# MCU089A_XDS110_USB_Power.net
KiCad netlist of a schematic drawn in Altium Designer
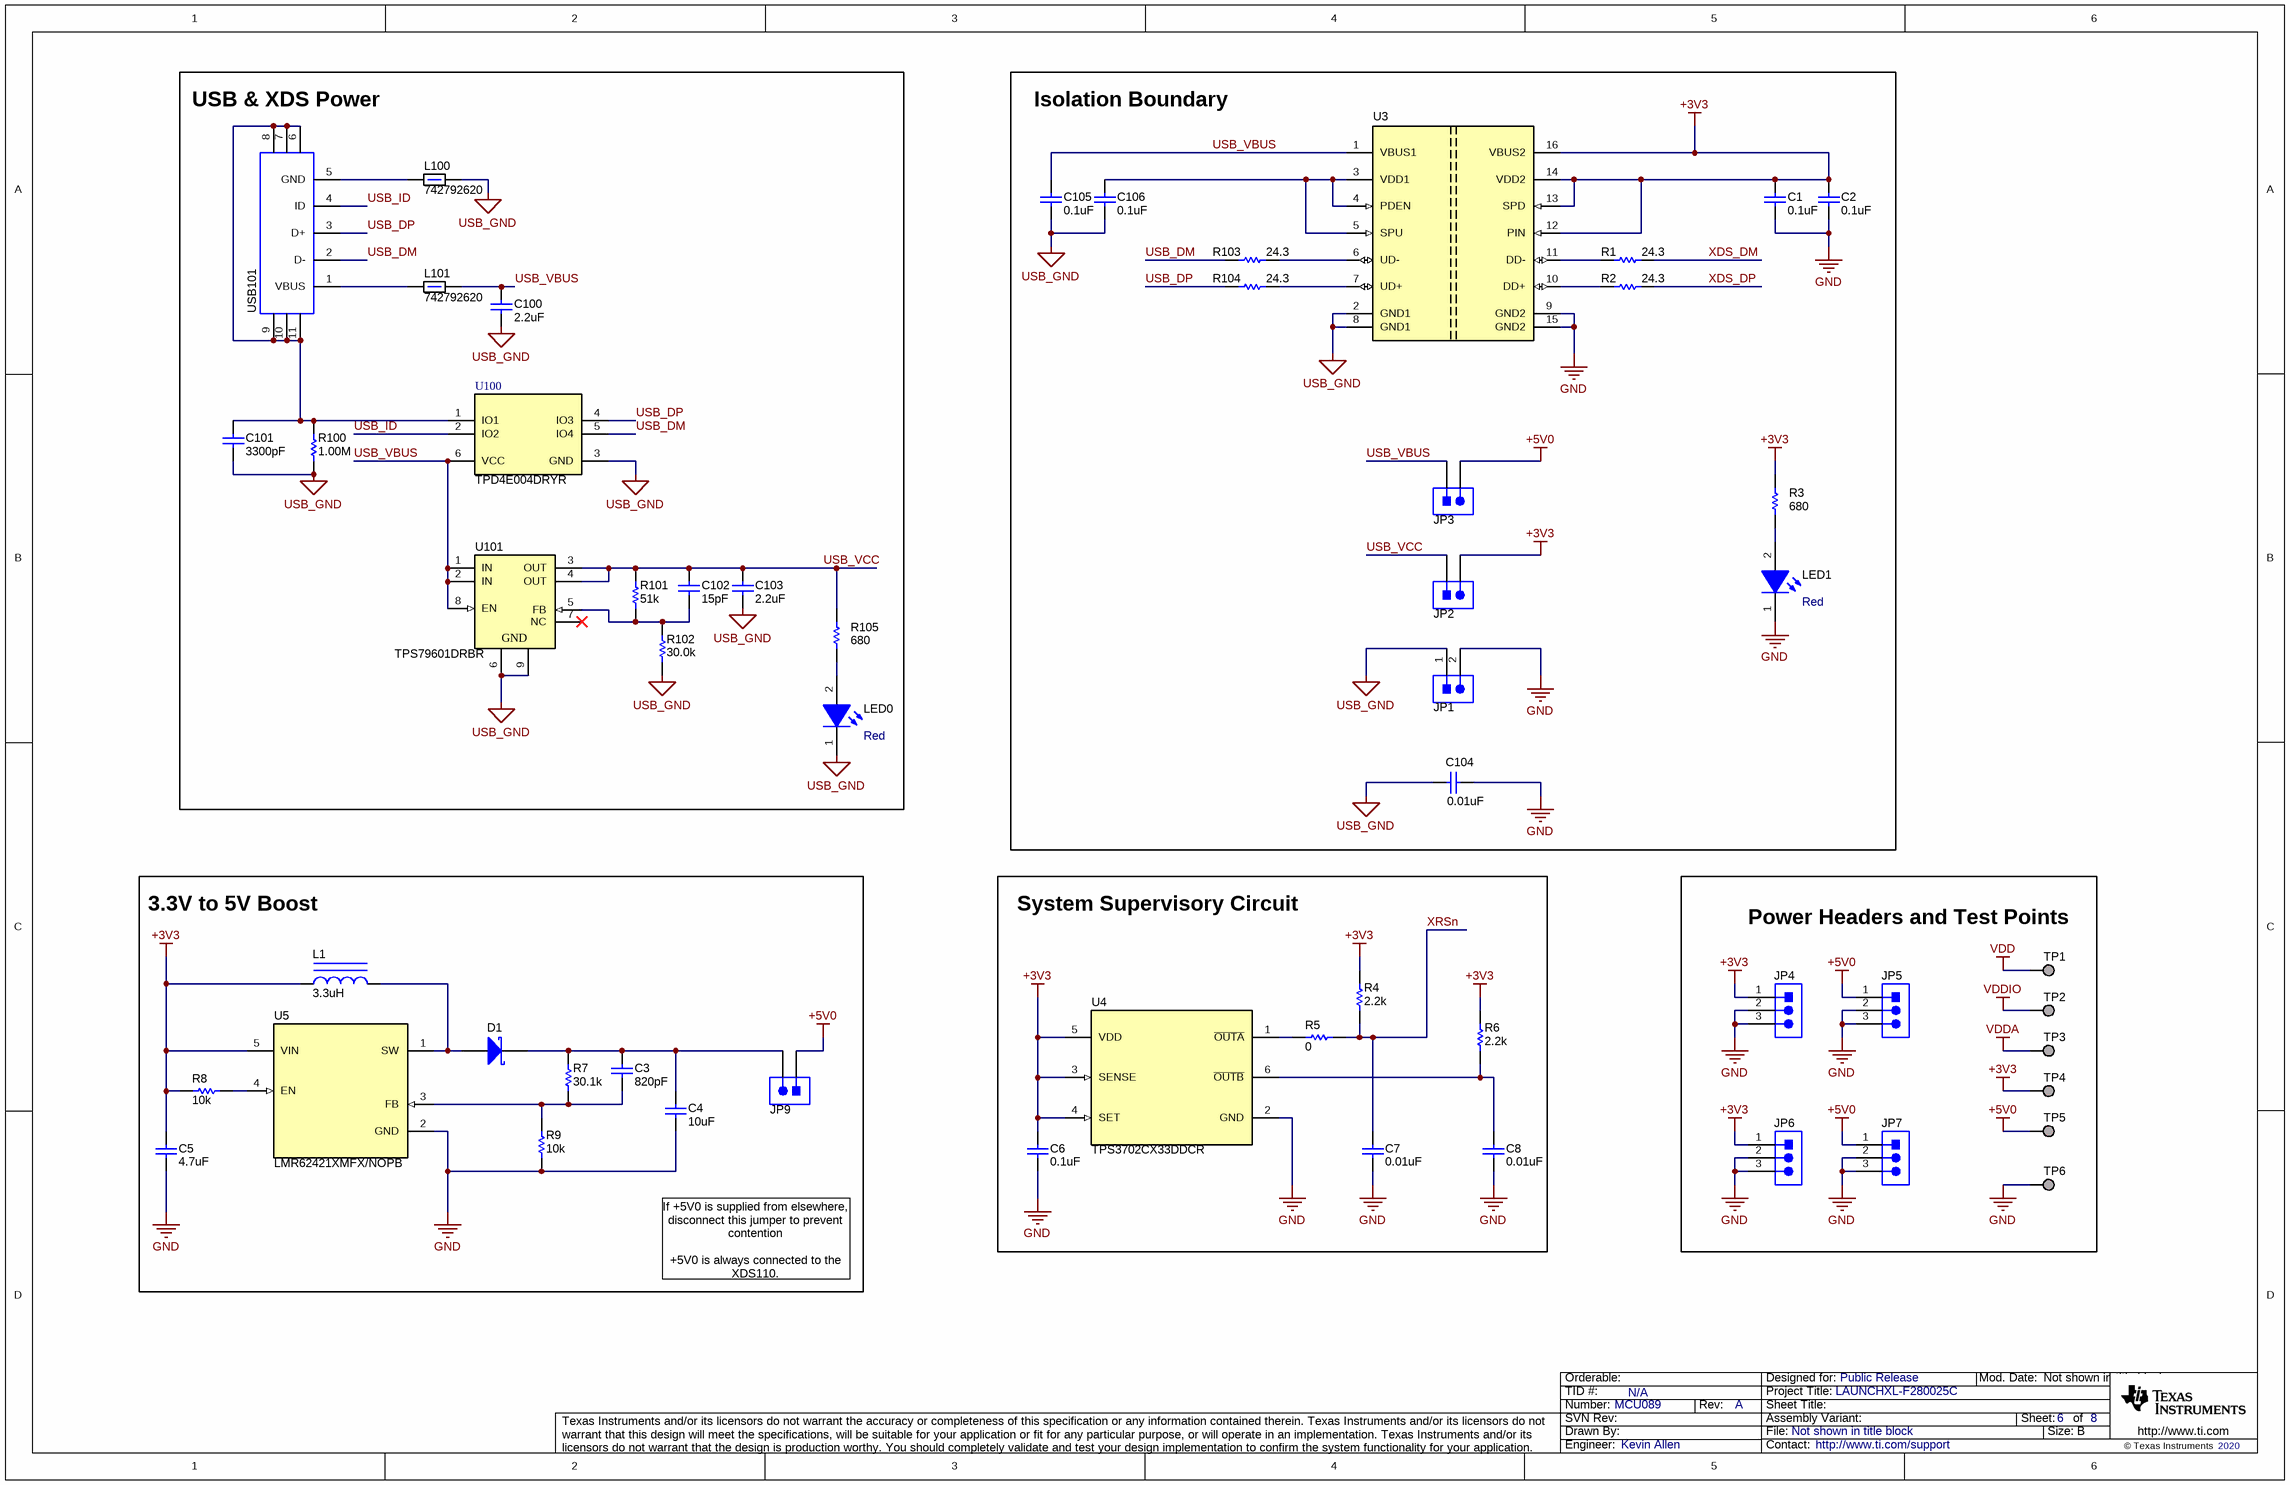
[diagram p0: MCU089A_XDS110_USB_Power.SchDoc]

(export (version "E")
  (design (tool "Eeschema 10.0.6"))
  (components
    (comp (ref "C1")
      (value "GRM155R71A104KA01D")
      (footprint "0402")
      (description "CAP, CERM, 0.1 uF, 10 V, +/- 10%, X7R, 0402")
      (fields
        (field (name "VALUEDISPLAYED") "0.1uF")
        (field (name "MANUFACTURER") "MuRata")
        (field (name "PUBLISHER") "Texas Instruments")
      )
      (libsource (lib "Altium Vault - TI") (part "Capacitor"))
    )
    (comp (ref "C2")
      (value "GRM155R71A104KA01D")
      (footprint "0402")
      (description "CAP, CERM, 0.1 uF, 10 V, +/- 10%, X7R, 0402")
      (fields
        (field (name "VALUEDISPLAYED") "0.1uF")
        (field (name "MANUFACTURER") "MuRata")
        (field (name "PUBLISHER") "Texas Instruments")
      )
      (libsource (lib "Altium Vault - TI") (part "Capacitor"))
    )
    (comp (ref "C3")
      (value "GRM1555C1E821JA01D")
      (footprint "0402")
      (description "CAP, CERM, 820 pF, 25 V, +/- 5%, C0G/NP0, 0402")
      (fields
        (field (name "MANUFACTURER") "MuRata")
        (field (name "VALUEDISPLAYED") "820pF")
        (field (name "PUBLISHER") "Texas Instruments")
      )
      (libsource (lib "Altium Vault - TI") (part "Capacitor"))
    )
    (comp (ref "C4")
      (value "885012209028")
      (footprint "1210_220")
      (description "CAP, CERM, 10 uF, 25 V,+/- 10%, X7R, 1210")
      (fields
        (field (name "VALUEDISPLAYED") "10uF")
        (field (name "MANUFACTURER") "Wurth Elektronik")
        (field (name "PUBLISHER") "Texas Instruments")
      )
      (libsource (lib "Altium Vault - TI") (part "Capacitor"))
    )
    (comp (ref "C5")
      (value "885012105008")
      (footprint "0402")
      (description "CAP, CERM, 4.7 uF, 6.3 V, +/- 20%, X5R, 0402")
      (fields
        (field (name "VALUEDISPLAYED") "4.7uF")
        (field (name "MANUFACTURER") "Wurth Elektronik")
        (field (name "PUBLISHER") "Texas Instruments")
      )
      (libsource (lib "Altium Vault - TI") (part "Capacitor"))
    )
    (comp (ref "C6")
      (value "GRM155R71A104KA01D")
      (footprint "0402")
      (description "CAP, CERM, 0.1 uF, 10 V, +/- 10%, X7R, 0402")
      (fields
        (field (name "VALUEDISPLAYED") "0.1uF")
        (field (name "MANUFACTURER") "MuRata")
        (field (name "PUBLISHER") "Texas Instruments")
      )
      (libsource (lib "Altium Vault - TI") (part "Capacitor"))
    )
    (comp (ref "C7")
      (value "GRM155R71E103KA01D")
      (footprint "0402")
      (description "CAP, CERM, 0.01 uF, 25 V, +/- 10%, X7R, 0402")
      (fields
        (field (name "VALUEDISPLAYED") "0.01uF")
        (field (name "MANUFACTURER") "MuRata")
        (field (name "PUBLISHER") "Texas Instruments")
      )
      (libsource (lib "Altium Vault - TI") (part "Capacitor"))
    )
    (comp (ref "C8")
      (value "GRM155R71E103KA01D")
      (footprint "0402")
      (description "CAP, CERM, 0.01 uF, 25 V, +/- 10%, X7R, 0402")
      (fields
        (field (name "VALUEDISPLAYED") "0.01uF")
        (field (name "MANUFACTURER") "MuRata")
        (field (name "PUBLISHER") "Texas Instruments")
      )
      (libsource (lib "Altium Vault - TI") (part "Capacitor"))
    )
    (comp (ref "C100")
      (value "GRM155R60J225KE95D")
      (footprint "0402")
      (description "CAP, CERM, 2.2 uF, 6.3 V, +/- 10%, X5R, 0402")
      (fields
        (field (name "VALUEDISPLAYED") "2.2uF")
        (field (name "MANUFACTURER") "MuRata")
        (field (name "PUBLISHER") "Texas Instruments")
      )
      (libsource (lib "Altium Vault - TI") (part "Capacitor"))
    )
    (comp (ref "C101")
      (value "GRM155R71H332KA01D")
      (footprint "0402")
      (description "CAP, CERM, 3300 pF, 50 V, +/- 10%, X7R, 0402")
      (fields
        (field (name "VALUEDISPLAYED") "3300pF")
        (field (name "MANUFACTURER") "MuRata")
        (field (name "PUBLISHER") "Texas Instruments")
      )
      (libsource (lib "Altium Vault - TI") (part "Capacitor"))
    )
    (comp (ref "C102")
      (value "885012005056")
      (footprint "0402")
      (description "CAP, CERM, 15 pF, 50 V, +/- 5%, C0G/NP0, 0402")
      (fields
        (field (name "VALUEDISPLAYED") "15pF")
        (field (name "MANUFACTURER") "Wurth Elektronik")
        (field (name "PUBLISHER") "Texas Instruments")
      )
      (libsource (lib "Altium Vault - TI") (part "Capacitor"))
    )
    (comp (ref "C103")
      (value "GRM155R60J225KE95D")
      (footprint "0402")
      (description "CAP, CERM, 2.2 uF, 6.3 V, +/- 10%, X5R, 0402")
      (fields
        (field (name "VALUEDISPLAYED") "2.2uF")
        (field (name "MANUFACTURER") "MuRata")
        (field (name "PUBLISHER") "Texas Instruments")
      )
      (libsource (lib "Altium Vault - TI") (part "Capacitor"))
    )
    (comp (ref "C104")
      (value "1812SC103KAT1A")
      (footprint "1812")
      (description "CAP, CERM, 0.01 uF, 1500 V, +/- 10%, X7R, 1812")
      (fields
        (field (name "MANUFACTURER") "AVX")
        (field (name "VALUEDISPLAYED") "0.01uF")
        (field (name "PUBLISHER") "Texas Instruments")
      )
      (libsource (lib "Altium Vault - TI") (part "Capacitor"))
    )
    (comp (ref "C105")
      (value "GRM155R71A104KA01D")
      (footprint "0402")
      (description "CAP, CERM, 0.1 uF, 10 V, +/- 10%, X7R, 0402")
      (fields
        (field (name "VALUEDISPLAYED") "0.1uF")
        (field (name "MANUFACTURER") "MuRata")
        (field (name "PUBLISHER") "Texas Instruments")
      )
      (libsource (lib "Altium Vault - TI") (part "Capacitor"))
    )
    (comp (ref "C106")
      (value "GRM155R71A104KA01D")
      (footprint "0402")
      (description "CAP, CERM, 0.1 uF, 10 V, +/- 10%, X7R, 0402")
      (fields
        (field (name "VALUEDISPLAYED") "0.1uF")
        (field (name "MANUFACTURER") "MuRata")
        (field (name "PUBLISHER") "Texas Instruments")
      )
      (libsource (lib "Altium Vault - TI") (part "Capacitor"))
    )
    (comp (ref "D1")
      (value "1N5819HW-7-F")
      (footprint "SOD-123")
      (description "Diode, Schottky, 40 V, 1 A, SOD-123")
      (fields (field (name "MANUFACTURER") "Diodes Inc."))
      (libsource (lib "Altium Vault - TI") (part "DIODE_SCHOTTKY"))
    )
    (comp (ref "JP1")
      (value "61300211121")
      (footprint "WURTH_61300211121")
      (description "Header, 2.54 mm, 2x1, Gold, TH")
      (fields (field (name "MANUFACTURER") "Wurth Elektronik") (field (name "PUBLISHER") "Texas Instruments"))
      (libsource (lib "Altium Vault - TI") (part "Header_2x1"))
    )
    (comp (ref "JP2")
      (value "61300211121")
      (footprint "WURTH_61300211121")
      (description "Header, 2.54 mm, 2x1, Gold, TH")
      (fields (field (name "MANUFACTURER") "Wurth Elektronik") (field (name "PUBLISHER") "Texas Instruments"))
      (libsource (lib "") (part "CMP-0054794-1_1"))
    )
    (comp (ref "JP3")
      (value "61300211121")
      (footprint "WURTH_61300211121")
      (description "Header, 2.54 mm, 2x1, Gold, TH")
      (fields (field (name "MANUFACTURER") "Wurth Elektronik") (field (name "PUBLISHER") "Texas Instruments"))
      (libsource (lib "") (part "CMP-0054794-1_1"))
    )
    (comp (ref "JP4")
      (value "61300311121")
      (footprint "WURTH_61300311121")
      (description "Header, 2.54 mm, 3x1, Gold, TH")
      (fields (field (name "MANUFACTURER") "Wurth Elektronik") (field (name "PUBLISHER") "Texas Instruments"))
      (libsource (lib "Altium Vault - TI") (part "Header_3x1"))
    )
    (comp (ref "JP5")
      (value "61300311121")
      (footprint "WURTH_61300311121")
      (description "Header, 2.54 mm, 3x1, Gold, TH")
      (fields (field (name "MANUFACTURER") "Wurth Elektronik") (field (name "PUBLISHER") "Texas Instruments"))
      (libsource (lib "Altium Vault - TI") (part "Header_3x1"))
    )
    (comp (ref "JP6")
      (value "61300311121")
      (footprint "WURTH_61300311121")
      (description "Header, 2.54 mm, 3x1, Gold, TH")
      (fields (field (name "MANUFACTURER") "Wurth Elektronik") (field (name "PUBLISHER") "Texas Instruments"))
      (libsource (lib "Altium Vault - TI") (part "Header_3x1"))
    )
    (comp (ref "JP7")
      (value "61300311121")
      (footprint "WURTH_61300311121")
      (description "Header, 2.54 mm, 3x1, Gold, TH")
      (fields (field (name "MANUFACTURER") "Wurth Elektronik") (field (name "PUBLISHER") "Texas Instruments"))
      (libsource (lib "Altium Vault - TI") (part "Header_3x1"))
    )
    (comp (ref "JP9")
      (value "61300211121")
      (footprint "WURTH_61300211121")
      (description "Header, 2.54 mm, 2x1, Gold, TH")
      (fields (field (name "MANUFACTURER") "Wurth Elektronik") (field (name "PUBLISHER") "Texas Instruments"))
      (libsource (lib "Altium Vault - TI") (part "CMP-0054794-1"))
    )
    (comp (ref "L1")
      (value "744025003")
      (footprint "WE-TPC_2828")
      (description "Inductor, Shielded Drum Core, Ferrite, 3.3 uH, 1.5 A, 0.085 ohm, SMD")
      (fields
        (field (name "VALUEDISPLAYED") "3.3uH")
        (field (name "MANUFACTURER") "Wurth Elektronik")
        (field (name "PUBLISHER") "Texas Instruments")
      )
      (libsource (lib "Altium Vault - TI") (part "Inductor_Iron"))
    )
    (comp (ref "L100")
      (value "742792620")
      (footprint "0603")
      (description "Ferrite Bead, 100 ohm @ 100 MHz, 0.5 A, 0603")
      (fields (field (name "MANUFACTURER") "Wurth Elektronik") (field (name "PUBLISHER") "Texas Instruments"))
      (libsource (lib "Altium Vault - TI") (part "Ferrite_Bead"))
    )
    (comp (ref "L101")
      (value "742792620")
      (footprint "0603")
      (description "Ferrite Bead, 100 ohm @ 100 MHz, 0.5 A, 0603")
      (fields (field (name "MANUFACTURER") "Wurth Elektronik") (field (name "PUBLISHER") "Texas Instruments"))
      (libsource (lib "Altium Vault - TI") (part "Ferrite_Bead"))
    )
    (comp (ref "LED0")
      (value "Red")
      (footprint "WL-SMCW_RED_0805")
      (description "LED, Red, SMD")
      (fields (field (name "MANUFACTURER") "Wurth Elektronik") (field (name "PARTNUMBER") "150080SS75000"))
      (libsource (lib "Altium Vault - TI") (part "LED_A2_K1"))
    )
    (comp (ref "LED1")
      (value "Red")
      (footprint "WL-SMCW_RED_0805")
      (description "LED, Red, SMD")
      (fields (field (name "MANUFACTURER") "Wurth Elektronik") (field (name "PARTNUMBER") "150080SS75000"))
      (libsource (lib "Altium Vault - TI") (part "LED_A2_K1"))
    )
    (comp (ref "R1")
      (value "CRCW040224R3FKED")
      (footprint "0402")
      (description "RES, 24.3, 1%, 0.063 W, AEC-Q200 Grade 0, 0402")
      (fields (field (name "VALUEDISPLAYED") "24.3") (field (name "MANUFACTURER") "Vishay-Dale"))
      (libsource (lib "Altium Vault - TI") (part "Resistor"))
    )
    (comp (ref "R2")
      (value "CRCW040224R3FKED")
      (footprint "0402")
      (description "RES, 24.3, 1%, 0.063 W, AEC-Q200 Grade 0, 0402")
      (fields (field (name "VALUEDISPLAYED") "24.3") (field (name "MANUFACTURER") "Vishay-Dale"))
      (libsource (lib "Altium Vault - TI") (part "Resistor"))
    )
    (comp (ref "R3")
      (value "CRCW0402680RJNED")
      (footprint "0402")
      (description "RES, 680, 5%, 0.063 W, AEC-Q200 Grade 0, 0402")
      (fields (field (name "MANUFACTURER") "Vishay-Dale") (field (name "VALUEDISPLAYED") "680"))
      (libsource (lib "Altium Vault - TI") (part "CMP-0026962-3"))
    )
    (comp (ref "R4")
      (value "CRCW04022K20JNED")
      (footprint "0402")
      (description "RES, 2.2 k, 5%, 0.063 W, AEC-Q200 Grade 0, 0402")
      (fields (field (name "VALUEDISPLAYED") "2.2k") (field (name "MANUFACTURER") "Vishay-Dale"))
      (libsource (lib "Altium Vault - TI") (part "Resistor"))
    )
    (comp (ref "R5")
      (value "CRCW04020000Z0ED")
      (footprint "0402")
      (description "RES, 0, 5%, 0.063 W, AEC-Q200 Grade 0, 0402")
      (fields (field (name "VALUEDISPLAYED") "0") (field (name "MANUFACTURER") "Vishay-Dale"))
      (libsource (lib "Altium Vault - TI") (part "Resistor"))
    )
    (comp (ref "R6")
      (value "CRCW06032K20JNEA")
      (footprint "0603")
      (description "RES, 2.2 k, 5%, 0.1 W, AEC-Q200 Grade 0, 0603")
      (fields (field (name "VALUEDISPLAYED") "2.2k") (field (name "MANUFACTURER") "Vishay-Dale"))
      (libsource (lib "Altium Vault - TI") (part "Resistor"))
    )
    (comp (ref "R7")
      (value "RC0402FR-0730K1L")
      (footprint "0402")
      (description "RES, 30.1 k, 1%, 0.063 W, 0402")
      (fields
        (field (name "VALUEDISPLAYED") "30.1k")
        (field (name "MANUFACTURER") "Yageo America")
        (field (name "PUBLISHER") "Texas Instruments")
      )
      (libsource (lib "Altium Vault - TI") (part "Resistor"))
    )
    (comp (ref "R8")
      (value "CRCW040210K0JNED")
      (footprint "0402")
      (description "RES, 10 k, 5%, 0.063 W, AEC-Q200 Grade 0, 0402")
      (fields (field (name "VALUEDISPLAYED") "10k") (field (name "MANUFACTURER") "Vishay-Dale"))
      (libsource (lib "Altium Vault - TI") (part "Resistor"))
    )
    (comp (ref "R9")
      (value "CRCW040210K0JNED")
      (footprint "0402")
      (description "RES, 10 k, 5%, 0.063 W, AEC-Q200 Grade 0, 0402")
      (fields (field (name "VALUEDISPLAYED") "10k") (field (name "MANUFACTURER") "Vishay-Dale"))
      (libsource (lib "Altium Vault - TI") (part "Resistor"))
    )
    (comp (ref "R100")
      (value "CRCW04021M00FKED")
      (footprint "0402")
      (description "RES, 1.00 M, 1%, 0.063 W, AEC-Q200 Grade 0, 0402")
      (fields (field (name "VALUEDISPLAYED") "1.00M") (field (name "MANUFACTURER") "Vishay-Dale"))
      (libsource (lib "Altium Vault - TI") (part "Resistor"))
    )
    (comp (ref "R101")
      (value "CRCW040251K0FKED")
      (footprint "0402")
      (description "RES Thick Film SMD 51kΩ 1% 1/16W 0402 100ppm/K")
      (fields (field (name "MANUFACTURER") "Vishay") (field (name "VALUEDISPLAYED") "51k"))
      (libsource (lib "Altium Vault - TI") (part "Resistor"))
    )
    (comp (ref "R102")
      (value "CRCW040230K0FKED")
      (footprint "0402")
      (description "RES, 30.0 k, 1%, 0.063 W, AEC-Q200 Grade 0, 0402")
      (fields (field (name "MANUFACTURER") "Vishay-Dale") (field (name "VALUEDISPLAYED") "30.0k"))
      (libsource (lib "Altium Vault - TI") (part "Resistor"))
    )
    (comp (ref "R103")
      (value "CRCW040224R3FKED")
      (footprint "0402")
      (description "RES, 24.3, 1%, 0.063 W, AEC-Q200 Grade 0, 0402")
      (fields (field (name "VALUEDISPLAYED") "24.3") (field (name "MANUFACTURER") "Vishay-Dale"))
      (libsource (lib "Altium Vault - TI") (part "Resistor"))
    )
    (comp (ref "R104")
      (value "CRCW040224R3FKED")
      (footprint "0402")
      (description "RES, 24.3, 1%, 0.063 W, AEC-Q200 Grade 0, 0402")
      (fields (field (name "VALUEDISPLAYED") "24.3") (field (name "MANUFACTURER") "Vishay-Dale"))
      (libsource (lib "Altium Vault - TI") (part "Resistor"))
    )
    (comp (ref "R105")
      (value "CRCW0402680RJNED")
      (footprint "0402")
      (description "RES, 680, 5%, 0.063 W, AEC-Q200 Grade 0, 0402")
      (fields (field (name "MANUFACTURER") "Vishay-Dale") (field (name "VALUEDISPLAYED") "680"))
      (libsource (lib "Altium Vault - TI") (part "CMP-0026962-3"))
    )
    (comp (ref "TP1")
      (value "TESTPOINT")
      (footprint "TP_50MIL-25MILHOLE")
      (description "TEST POINT.  No entry in BOM.")
      (libsource (lib "Altium Vault - TI") (part "TESTPOINT"))
    )
    (comp (ref "TP2")
      (value "TESTPOINT")
      (footprint "TP_50MIL-25MILHOLE")
      (description "TEST POINT.  No entry in BOM.")
      (libsource (lib "Altium Vault - TI") (part "TESTPOINT"))
    )
    (comp (ref "TP3")
      (value "TESTPOINT")
      (footprint "TP_50MIL-25MILHOLE")
      (description "TEST POINT.  No entry in BOM.")
      (libsource (lib "Altium Vault - TI") (part "TESTPOINT"))
    )
    (comp (ref "TP4")
      (value "TESTPOINT")
      (footprint "TP_50MIL-25MILHOLE")
      (description "TEST POINT.  No entry in BOM.")
      (libsource (lib "Altium Vault - TI") (part "TESTPOINT"))
    )
    (comp (ref "TP5")
      (value "TESTPOINT")
      (footprint "TP_50MIL-25MILHOLE")
      (description "TEST POINT.  No entry in BOM.")
      (libsource (lib "Altium Vault - TI") (part "TESTPOINT"))
    )
    (comp (ref "TP6")
      (value "TESTPOINT")
      (footprint "TP_50MIL-25MILHOLE")
      (description "TEST POINT.  No entry in BOM.")
      (libsource (lib "Altium Vault - TI") (part "TESTPOINT"))
    )
    (comp (ref "U3")
      (value "ADuM3160BRWZ")
      (footprint "SOIC-16")
      (description "Full/Low Speed 2.5 kV USB Digital Isolator, SOIC-16")
      (fields (field (name "MANUFACTURER") "Analog Devices") (field (name "PUBLISHER") "Texas Instruments"))
      (libsource (lib "Altium Vault - TI") (part "ADuM3160"))
    )
    (comp (ref "U4")
      (value "TPS3702CX33DDCR")
      (footprint "DDC0006A_N")
      (description "High-Accuracy, Fixed-Threshold OV/UV Monitor, DDC0006A (SOT-23-T-6)")
      (fields
        (field (name "ALTERNATE PARTNUMBER") "TPS3702CX33DDCT")
        (field (name "MANUFACTURER") "Texas Instruments")
        (field (name "PUBLISHER") "Texas Instruments")
      )
      (libsource (lib "Altium Vault - TI") (part "TPS3702"))
    )
    (comp (ref "U5")
      (value "LMR62421XMFX/NOPB")
      (footprint "DBV0005A_N")
      (description "SIMPLE SWITCHER 2.7V to 5.5V, 2.1A Step-Up Regulator in SOT-23, DBV0005A (SOT-23-5)")
      (fields
        (field (name "ALTERNATE PARTNUMBER") "LMR62421XMFE/NOPB")
        (field (name "MANUFACTURER") "Texas Instruments")
        (field (name "PUBLISHER") "Texas Instruments")
      )
      (libsource (lib "Altium Vault - TI") (part "LMR62421DBV"))
    )
    (comp (ref "U100")
      (value "TPD4E004DRYR")
      (footprint "DRY0006A")
      (description "4-Channel ESD Protection Array for High-Speed Data Interfaces, DRY0006A (USON-6)")
      (fields (field (name "MANUFACTURER") "Texas Instruments") (field (name "PARTNUMBER") "TPD4E004DRYR"))
      (libsource (lib "Altium Vault - TI") (part "TI-TPD4E004-SON_DRY-6"))
    )
    (comp (ref "U101")
      (value "TPS79601DRBR")
      (footprint "DRB0008B")
      (fields (field (name "MANUFACTURER") "Texas Instruments"))
      (libsource (lib "Altium Vault - TI") (part "CMP-0036402-3"))
    )
    (comp (ref "USB101")
      (value "1051640001")
      (footprint "Molex_1051640001")
      (description "Receptacle, USB 2.0, Micro B, 5 Position, R/A, SMT")
      (fields (field (name "MANUFACTURER") "Molex") (field (name "PUBLISHER") "Texas Instruments"))
      (libsource (lib "Altium Vault - TI") (part "CONN_USB_MicroMini_6Shld"))
    )
  )
  (nets
    (net (code "1") (name "+3V3") (class "Default")
      (node (ref "C1") (pin "2") (pinfunction "2_2") (pintype "passive"))
      (node (ref "C2") (pin "2") (pinfunction "2_2") (pintype "passive"))
      (node (ref "C5") (pin "1") (pinfunction "1_1") (pintype "passive"))
      (node (ref "C6") (pin "2") (pinfunction "2_2") (pintype "passive"))
      (node (ref "JP2") (pin "2") (pinfunction "2_2") (pintype "passive"))
      (node (ref "JP4") (pin "1") (pinfunction "1_1") (pintype "passive"))
      (node (ref "JP6") (pin "1") (pinfunction "1_1") (pintype "passive"))
      (node (ref "L1") (pin "1") (pinfunction "1_1") (pintype "passive"))
      (node (ref "R3") (pin "2") (pinfunction "2_2") (pintype "passive"))
      (node (ref "R4") (pin "2") (pinfunction "2_2") (pintype "passive"))
      (node (ref "R6") (pin "2") (pinfunction "2_2") (pintype "passive"))
      (node (ref "R8") (pin "2") (pinfunction "2_2") (pintype "passive"))
      (node (ref "TP4") (pin "1") (pintype "passive"))
      (node (ref "U3") (pin "12") (pinfunction "PIN_12") (pintype "input"))
      (node (ref "U3") (pin "13") (pinfunction "SPD_13") (pintype "input"))
      (node (ref "U3") (pin "14") (pinfunction "VDD2_14") (pintype "power_in"))
      (node (ref "U3") (pin "16") (pinfunction "VBUS2_16") (pintype "power_in"))
      (node (ref "U4") (pin "3") (pinfunction "SENSE_3") (pintype "input"))
      (node (ref "U4") (pin "4") (pinfunction "SET_4") (pintype "input"))
      (node (ref "U4") (pin "5") (pinfunction "VDD_5") (pintype "power_in"))
      (node (ref "U5") (pin "5") (pinfunction "VIN_5") (pintype "power_in"))
    )
    (net (code "2") (name "+5V0") (class "Default")
      (node (ref "JP3") (pin "2") (pinfunction "2_2") (pintype "passive"))
      (node (ref "JP5") (pin "1") (pinfunction "1_1") (pintype "passive"))
      (node (ref "JP7") (pin "1") (pinfunction "1_1") (pintype "passive"))
      (node (ref "JP9") (pin "1") (pinfunction "1_1") (pintype "passive"))
      (node (ref "TP5") (pin "1") (pintype "passive"))
    )
    (net (code "3") (name "/USB_DM") (class "Default")
      (node (ref "R103") (pin "1") (pinfunction "1_1") (pintype "passive"))
      (node (ref "U100") (pin "5") (pinfunction "IO4_5") (pintype "passive"))
      (node (ref "USB101") (pin "2") (pinfunction "D-_2") (pintype "passive"))
    )
    (net (code "4") (name "/USB_DP") (class "Default")
      (node (ref "R104") (pin "1") (pinfunction "1_1") (pintype "passive"))
      (node (ref "U100") (pin "4") (pinfunction "IO3_4") (pintype "passive"))
      (node (ref "USB101") (pin "3") (pinfunction "D+_3") (pintype "passive"))
    )
    (net (code "5") (name "/USB_ID") (class "Default")
      (node (ref "U100") (pin "2") (pinfunction "IO2_2") (pintype "passive"))
      (node (ref "USB101") (pin "4") (pinfunction "ID_4") (pintype "passive"))
    )
    (net (code "6") (name "/USB_VBUS") (class "Default")
      (node (ref "C100") (pin "1") (pinfunction "1_1") (pintype "passive"))
      (node (ref "C105") (pin "2") (pinfunction "2_2") (pintype "passive"))
      (node (ref "JP3") (pin "1") (pinfunction "1_1") (pintype "passive"))
      (node (ref "L101") (pin "2") (pinfunction "2_2") (pintype "passive"))
      (node (ref "U100") (pin "6") (pinfunction "VCC_6") (pintype "power_in"))
      (node (ref "U101") (pin "1") (pinfunction "IN_1") (pintype "power_in"))
      (node (ref "U101") (pin "2") (pinfunction "IN_2") (pintype "power_in"))
      (node (ref "U101") (pin "8") (pinfunction "EN_8") (pintype "input"))
      (node (ref "U3") (pin "1") (pinfunction "VBUS1_1") (pintype "power_in"))
    )
    (net (code "7") (name "/USB_VCC") (class "Default")
      (node (ref "C102") (pin "1") (pinfunction "1_1") (pintype "passive"))
      (node (ref "C103") (pin "1") (pinfunction "1_1") (pintype "passive"))
      (node (ref "JP2") (pin "1") (pinfunction "1_1") (pintype "passive"))
      (node (ref "R101") (pin "2") (pinfunction "2_2") (pintype "passive"))
      (node (ref "R105") (pin "2") (pinfunction "2_2") (pintype "passive"))
      (node (ref "U101") (pin "3") (pinfunction "OUT_3") (pintype "power_in"))
      (node (ref "U101") (pin "4") (pinfunction "OUT_4") (pintype "power_in"))
    )
    (net (code "8") (name "/XDS_DM") (class "Default")
      (node (ref "R1") (pin "2") (pinfunction "2_2") (pintype "passive"))
    )
    (net (code "9") (name "/XDS_DP") (class "Default")
      (node (ref "R2") (pin "2") (pinfunction "2_2") (pintype "passive"))
    )
    (net (code "10") (name "/XRSn") (class "Default")
      (node (ref "C7") (pin "1") (pinfunction "1_1") (pintype "passive"))
      (node (ref "R4") (pin "1") (pinfunction "1_1") (pintype "passive"))
      (node (ref "R5") (pin "2") (pinfunction "2_2") (pintype "passive"))
    )
    (net (code "11") (name "GND") (class "Default")
      (node (ref "C1") (pin "1") (pinfunction "1_1") (pintype "passive"))
      (node (ref "C104") (pin "1") (pinfunction "1_1") (pintype "passive"))
      (node (ref "C2") (pin "1") (pinfunction "1_1") (pintype "passive"))
      (node (ref "C4") (pin "2") (pinfunction "2_2") (pintype "passive"))
      (node (ref "C5") (pin "2") (pinfunction "2_2") (pintype "passive"))
      (node (ref "C6") (pin "1") (pinfunction "1_1") (pintype "passive"))
      (node (ref "C7") (pin "2") (pinfunction "2_2") (pintype "passive"))
      (node (ref "C8") (pin "2") (pinfunction "2_2") (pintype "passive"))
      (node (ref "JP1") (pin "2") (pinfunction "2_2") (pintype "passive"))
      (node (ref "JP4") (pin "2") (pinfunction "2_2") (pintype "passive"))
      (node (ref "JP4") (pin "3") (pinfunction "3_3") (pintype "passive"))
      (node (ref "JP5") (pin "2") (pinfunction "2_2") (pintype "passive"))
      (node (ref "JP5") (pin "3") (pinfunction "3_3") (pintype "passive"))
      (node (ref "JP6") (pin "2") (pinfunction "2_2") (pintype "passive"))
      (node (ref "JP6") (pin "3") (pinfunction "3_3") (pintype "passive"))
      (node (ref "JP7") (pin "2") (pinfunction "2_2") (pintype "passive"))
      (node (ref "JP7") (pin "3") (pinfunction "3_3") (pintype "passive"))
      (node (ref "LED1") (pin "1") (pinfunction "K_1") (pintype "passive"))
      (node (ref "R9") (pin "1") (pinfunction "1_1") (pintype "passive"))
      (node (ref "TP6") (pin "1") (pintype "passive"))
      (node (ref "U3") (pin "15") (pinfunction "GND2_15") (pintype "power_in"))
      (node (ref "U3") (pin "9") (pinfunction "GND2_9") (pintype "power_in"))
      (node (ref "U4") (pin "2") (pinfunction "GND_2") (pintype "power_in"))
      (node (ref "U5") (pin "2") (pinfunction "GND_2") (pintype "power_in"))
    )
    (net (code "12") (name "Net-(D1-A)") (class "Default")
      (node (ref "D1") (pin "2") (pinfunction "A_2") (pintype "passive"))
      (node (ref "L1") (pin "2") (pinfunction "2_2") (pintype "passive"))
      (node (ref "U5") (pin "1") (pinfunction "SW_1") (pintype "power_in"))
    )
    (net (code "13") (name "Net-(D1-K)") (class "Default")
      (node (ref "C3") (pin "1") (pinfunction "1_1") (pintype "passive"))
      (node (ref "C4") (pin "1") (pinfunction "1_1") (pintype "passive"))
      (node (ref "D1") (pin "1") (pinfunction "K_1") (pintype "passive"))
      (node (ref "JP9") (pin "2") (pinfunction "2_2") (pintype "passive"))
      (node (ref "R7") (pin "2") (pinfunction "2_2") (pintype "passive"))
    )
    (net (code "14") (name "Net-(LED0-A)") (class "Default")
      (node (ref "LED0") (pin "2") (pinfunction "A_2") (pintype "passive"))
      (node (ref "R105") (pin "1") (pinfunction "1_1") (pintype "passive"))
    )
    (net (code "15") (name "Net-(LED1-A)") (class "Default")
      (node (ref "LED1") (pin "2") (pinfunction "A_2") (pintype "passive"))
      (node (ref "R3") (pin "1") (pinfunction "1_1") (pintype "passive"))
    )
    (net (code "16") (name "Net-(U3-DD+)") (class "Default")
      (node (ref "R2") (pin "1") (pinfunction "1_1") (pintype "passive"))
      (node (ref "U3") (pin "10") (pinfunction "DD+_10") (pintype "bidirectional"))
    )
    (net (code "17") (name "Net-(U3-DD-)") (class "Default")
      (node (ref "R1") (pin "1") (pinfunction "1_1") (pintype "passive"))
      (node (ref "U3") (pin "11") (pinfunction "DD-_11") (pintype "bidirectional"))
    )
    (net (code "18") (name "Net-(U3-PDEN)") (class "Default")
      (node (ref "C106") (pin "2") (pinfunction "2_2") (pintype "passive"))
      (node (ref "U3") (pin "3") (pinfunction "VDD1_3") (pintype "power_in"))
      (node (ref "U3") (pin "4") (pinfunction "PDEN_4") (pintype "input"))
      (node (ref "U3") (pin "5") (pinfunction "SPU_5") (pintype "input"))
    )
    (net (code "19") (name "Net-(U3-UD+)") (class "Default")
      (node (ref "R104") (pin "2") (pinfunction "2_2") (pintype "passive"))
      (node (ref "U3") (pin "7") (pinfunction "UD+_7") (pintype "bidirectional"))
    )
    (net (code "20") (name "Net-(U3-UD-)") (class "Default")
      (node (ref "R103") (pin "2") (pinfunction "2_2") (pintype "passive"))
      (node (ref "U3") (pin "6") (pinfunction "UD-_6") (pintype "bidirectional"))
    )
    (net (code "21") (name "Net-(U4-OUTA)") (class "Default")
      (node (ref "R5") (pin "1") (pinfunction "1_1") (pintype "passive"))
      (node (ref "U4") (pin "1") (pinfunction "OUTA_1") (pintype "open_collector"))
    )
    (net (code "22") (name "Net-(U4-OUTB)") (class "Default")
      (node (ref "C8") (pin "1") (pinfunction "1_1") (pintype "passive"))
      (node (ref "R6") (pin "1") (pinfunction "1_1") (pintype "passive"))
      (node (ref "U4") (pin "6") (pinfunction "OUTB_6") (pintype "open_collector"))
    )
    (net (code "23") (name "Net-(U5-EN)") (class "Default")
      (node (ref "R8") (pin "1") (pinfunction "1_1") (pintype "passive"))
      (node (ref "U5") (pin "4") (pinfunction "EN_4") (pintype "input"))
    )
    (net (code "24") (name "Net-(U5-FB)") (class "Default")
      (node (ref "C3") (pin "2") (pinfunction "2_2") (pintype "passive"))
      (node (ref "R7") (pin "1") (pinfunction "1_1") (pintype "passive"))
      (node (ref "R9") (pin "2") (pinfunction "2_2") (pintype "passive"))
      (node (ref "U5") (pin "3") (pinfunction "FB_3") (pintype "input"))
    )
    (net (code "25") (name "Net-(U100-IO1)") (class "Default")
      (node (ref "C101") (pin "1") (pinfunction "1_1") (pintype "passive"))
      (node (ref "R100") (pin "2") (pinfunction "2_2") (pintype "passive"))
      (node (ref "U100") (pin "1") (pinfunction "IO1_1") (pintype "passive"))
      (node (ref "USB101") (pin "10") (pinfunction "10_10") (pintype "passive"))
      (node (ref "USB101") (pin "11") (pinfunction "11_11") (pintype "passive"))
      (node (ref "USB101") (pin "6") (pinfunction "6_6") (pintype "passive"))
      (node (ref "USB101") (pin "7") (pinfunction "7_7") (pintype "passive"))
      (node (ref "USB101") (pin "8") (pinfunction "8_8") (pintype "passive"))
      (node (ref "USB101") (pin "9") (pinfunction "9_9") (pintype "passive"))
    )
    (net (code "26") (name "Net-(U101-FB)") (class "Default")
      (node (ref "C102") (pin "2") (pinfunction "2_2") (pintype "passive"))
      (node (ref "R101") (pin "1") (pinfunction "1_1") (pintype "passive"))
      (node (ref "R102") (pin "2") (pinfunction "2_2") (pintype "passive"))
      (node (ref "U101") (pin "5") (pinfunction "FB_5") (pintype "input"))
    )
    (net (code "27") (name "Net-(USB101-GND)") (class "Default")
      (node (ref "L100") (pin "1") (pinfunction "1_1") (pintype "passive"))
      (node (ref "USB101") (pin "5") (pinfunction "GND_5") (pintype "passive"))
    )
    (net (code "28") (name "Net-(USB101-VBUS)") (class "Default")
      (node (ref "L101") (pin "1") (pinfunction "1_1") (pintype "passive"))
      (node (ref "USB101") (pin "1") (pinfunction "VBUS_1") (pintype "passive"))
    )
    (net (code "29") (name "USB_GND") (class "Default")
      (node (ref "C100") (pin "2") (pinfunction "2_2") (pintype "passive"))
      (node (ref "C101") (pin "2") (pinfunction "2_2") (pintype "passive"))
      (node (ref "C103") (pin "2") (pinfunction "2_2") (pintype "passive"))
      (node (ref "C104") (pin "2") (pinfunction "2_2") (pintype "passive"))
      (node (ref "C105") (pin "1") (pinfunction "1_1") (pintype "passive"))
      (node (ref "C106") (pin "1") (pinfunction "1_1") (pintype "passive"))
      (node (ref "JP1") (pin "1") (pinfunction "1_1") (pintype "passive"))
      (node (ref "L100") (pin "2") (pinfunction "2_2") (pintype "passive"))
      (node (ref "LED0") (pin "1") (pinfunction "K_1") (pintype "passive"))
      (node (ref "R100") (pin "1") (pinfunction "1_1") (pintype "passive"))
      (node (ref "R102") (pin "1") (pinfunction "1_1") (pintype "passive"))
      (node (ref "U100") (pin "3") (pinfunction "GND_3") (pintype "power_in"))
      (node (ref "U101") (pin "6") (pinfunction "GND_6") (pintype "power_in"))
      (node (ref "U101") (pin "9") (pinfunction "GND_9") (pintype "power_in"))
      (node (ref "U3") (pin "2") (pinfunction "GND1_2") (pintype "power_in"))
      (node (ref "U3") (pin "8") (pinfunction "GND1_8") (pintype "power_in"))
    )
    (net (code "30") (name "VDD") (class "Default") (node (ref "TP1") (pin "1") (pintype "passive")))
    (net (code "31") (name "VDDA") (class "Default") (node (ref "TP3") (pin "1") (pintype "passive")))
    (net (code "32") (name "VDDIO") (class "Default") (node (ref "TP2") (pin "1") (pintype "passive")))
    (net (code "33") (name "unconnected-(U101-NC-Pad7)") (class "Default")
      (node (ref "U101") (pin "7") (pinfunction "NC_7") (pintype "passive+no_connect"))
    )
  )
)
